# FLASH.net
KiCad netlist of a schematic drawn in EAGLE
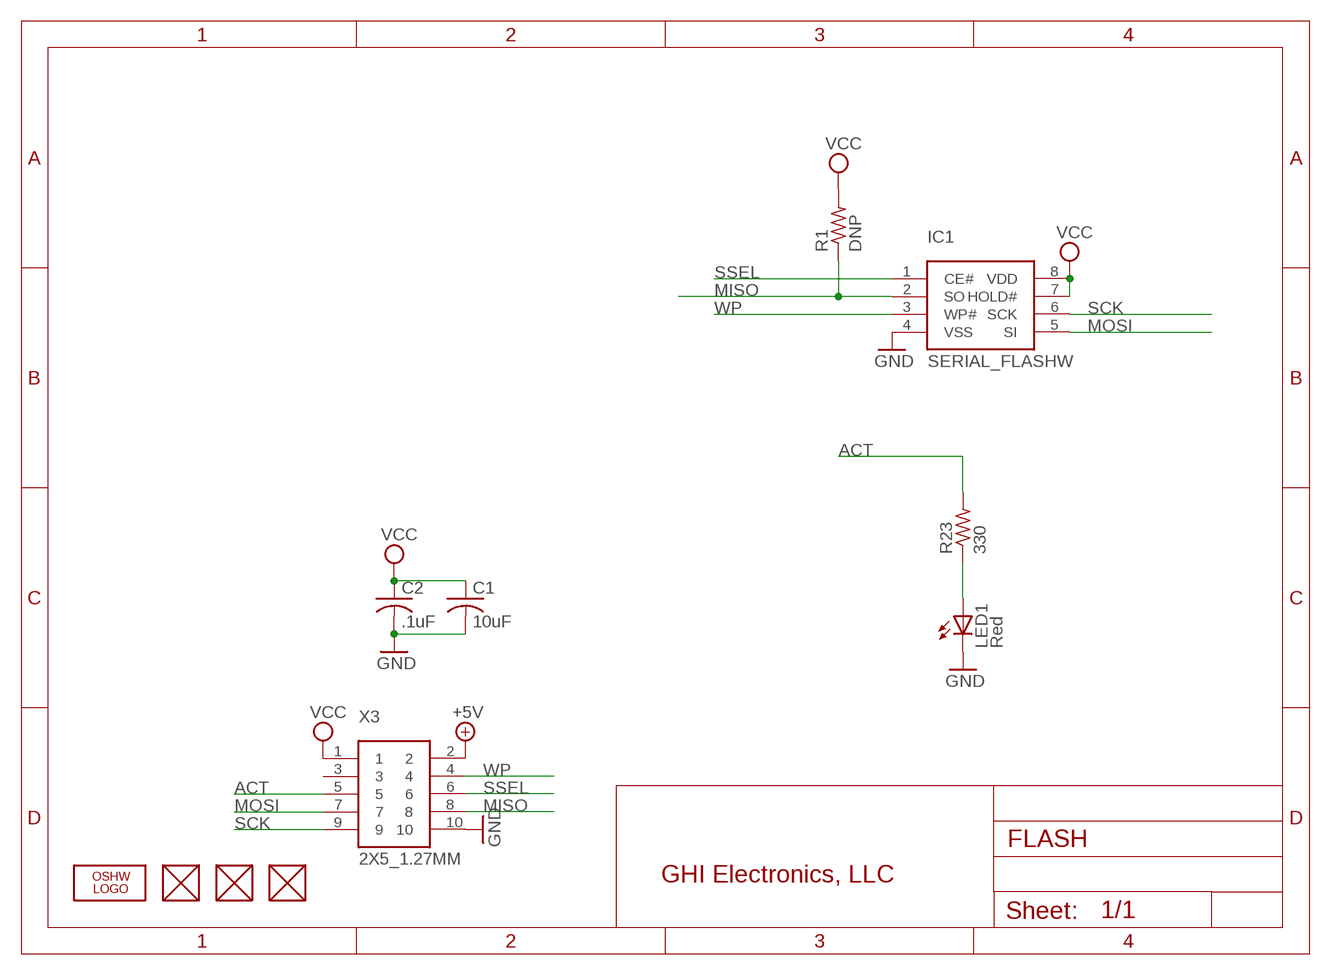
[diagram p0: schematic, sheet 1]

(export (version "E")
  (design (tool "Eeschema 10.0.6"))
  (components
    (comp (ref "C1")
      (value "10uF")
      (footprint "eagle-import:C0805K")
      (libsource (lib "eagle-import") (part "C-USC0805K"))
    )
    (comp (ref "C2")
      (value ".1uF")
      (footprint "eagle-import:C0603K")
      (libsource (lib "eagle-import") (part "C-USC0603K"))
    )
    (comp (ref "FUD1")
      (value "FIDUCIAL")
      (footprint "eagle-import:FIDUCIAL_40MIL")
      (libsource (lib "eagle-import") (part "FIDUCIAL"))
    )
    (comp (ref "FUD2")
      (value "FIDUCIAL")
      (footprint "eagle-import:FIDUCIAL_40MIL")
      (libsource (lib "eagle-import") (part "FIDUCIAL"))
    )
    (comp (ref "FUD3")
      (value "FIDUCIAL")
      (footprint "eagle-import:FIDUCIAL_40MIL")
      (libsource (lib "eagle-import") (part "FIDUCIAL"))
    )
    (comp (ref "IC1")
      (value "SERIAL_FLASHW")
      (footprint "eagle-import:SO8-WIDE")
      (libsource (lib "eagle-import") (part "SERIAL_FLASHW"))
    )
    (comp (ref "LED1")
      (value "Red")
      (footprint "eagle-import:CHIPLED_0805")
      (libsource (lib "eagle-import") (part "LEDCHIPLED_0805"))
    )
    (comp (ref "LOGO")
      (value "LOGO-OSHW-FILLX0200-NT")
      (footprint "eagle-import:OSHW_FILLX200_NOTEXT")
      (libsource (lib "eagle-import") (part "LOGO-OSHW-FILLX0200-NT"))
    )
    (comp (ref "R1")
      (value "DNP")
      (footprint "eagle-import:R0402")
      (libsource (lib "eagle-import") (part "R-US_R0402"))
    )
    (comp (ref "R23")
      (value "330")
      (footprint "eagle-import:R0603")
      (libsource (lib "eagle-import") (part "R-US_R0603"))
    )
    (comp (ref "X3")
      (value "2X5_1.27MM")
      (footprint "eagle-import:2X5_1.27MM")
      (libsource (lib "eagle-import") (part "2X5_1.27MM"))
    )
  )
  (nets
    (net (code "1") (name "+5V") (class "Default")
      (node (ref "X3") (pin "2") (pinfunction "2_2") (pintype "bidirectional"))
    )
    (net (code "2") (name "/ACT") (class "Default")
      (node (ref "R23") (pin "2") (pinfunction "2_2") (pintype "passive"))
      (node (ref "X3") (pin "5") (pinfunction "5_5") (pintype "bidirectional"))
    )
    (net (code "3") (name "/MISO") (class "Default")
      (node (ref "IC1") (pin "2") (pinfunction "SO_2") (pintype "bidirectional"))
      (node (ref "R1") (pin "1") (pinfunction "1_1") (pintype "passive"))
      (node (ref "X3") (pin "8") (pinfunction "8_8") (pintype "bidirectional"))
    )
    (net (code "4") (name "/MOSI") (class "Default")
      (node (ref "IC1") (pin "5") (pinfunction "SI_5") (pintype "bidirectional"))
      (node (ref "X3") (pin "7") (pinfunction "7_7") (pintype "bidirectional"))
    )
    (net (code "5") (name "/SCK") (class "Default")
      (node (ref "IC1") (pin "6") (pinfunction "SCK_6") (pintype "bidirectional"))
      (node (ref "X3") (pin "9") (pinfunction "9_9") (pintype "bidirectional"))
    )
    (net (code "6") (name "/SSEL") (class "Default")
      (node (ref "IC1") (pin "1") (pinfunction "CE#_1") (pintype "bidirectional"))
      (node (ref "X3") (pin "6") (pinfunction "6_6") (pintype "bidirectional"))
    )
    (net (code "7") (name "/WP") (class "Default")
      (node (ref "IC1") (pin "3") (pinfunction "WP#_3") (pintype "bidirectional"))
      (node (ref "X3") (pin "4") (pinfunction "4_4") (pintype "bidirectional"))
    )
    (net (code "8") (name "GND") (class "Default")
      (node (ref "C1") (pin "2") (pinfunction "2_2") (pintype "passive"))
      (node (ref "C2") (pin "2") (pinfunction "2_2") (pintype "passive"))
      (node (ref "IC1") (pin "4") (pinfunction "VSS_4") (pintype "bidirectional"))
      (node (ref "LED1") (pin "C") (pinfunction "C_C") (pintype "passive"))
      (node (ref "X3") (pin "10") (pinfunction "10_10") (pintype "bidirectional"))
    )
    (net (code "9") (name "Net-(LED1-PadA)") (class "Default")
      (node (ref "LED1") (pin "A") (pinfunction "A_A") (pintype "passive"))
      (node (ref "R23") (pin "1") (pinfunction "1_1") (pintype "passive"))
    )
    (net (code "10") (name "VCC") (class "Default")
      (node (ref "C1") (pin "1") (pinfunction "1_1") (pintype "passive"))
      (node (ref "C2") (pin "1") (pinfunction "1_1") (pintype "passive"))
      (node (ref "IC1") (pin "7") (pinfunction "HOLD#_7") (pintype "bidirectional"))
      (node (ref "IC1") (pin "8") (pinfunction "VDD_8") (pintype "bidirectional"))
      (node (ref "R1") (pin "2") (pinfunction "2_2") (pintype "passive"))
      (node (ref "X3") (pin "1") (pinfunction "1_1") (pintype "bidirectional"))
    )
    (net (code "11") (name "unconnected-(FUD1-PadP$1)") (class "Default")
      (node (ref "FUD1") (pin "P$1") (pinfunction "P$1_P$1") (pintype "no_connect"))
    )
    (net (code "12") (name "unconnected-(FUD2-PadP$1)") (class "Default")
      (node (ref "FUD2") (pin "P$1") (pinfunction "P$1_P$1") (pintype "no_connect"))
    )
    (net (code "13") (name "unconnected-(FUD3-PadP$1)") (class "Default")
      (node (ref "FUD3") (pin "P$1") (pinfunction "P$1_P$1") (pintype "no_connect"))
    )
    (net (code "14") (name "unconnected-(X3-Pad3)") (class "Default")
      (node (ref "X3") (pin "3") (pinfunction "3_3") (pintype "bidirectional"))
    )
  )
)
